# PCB.net
KiCad netlist of a schematic drawn in EAGLE
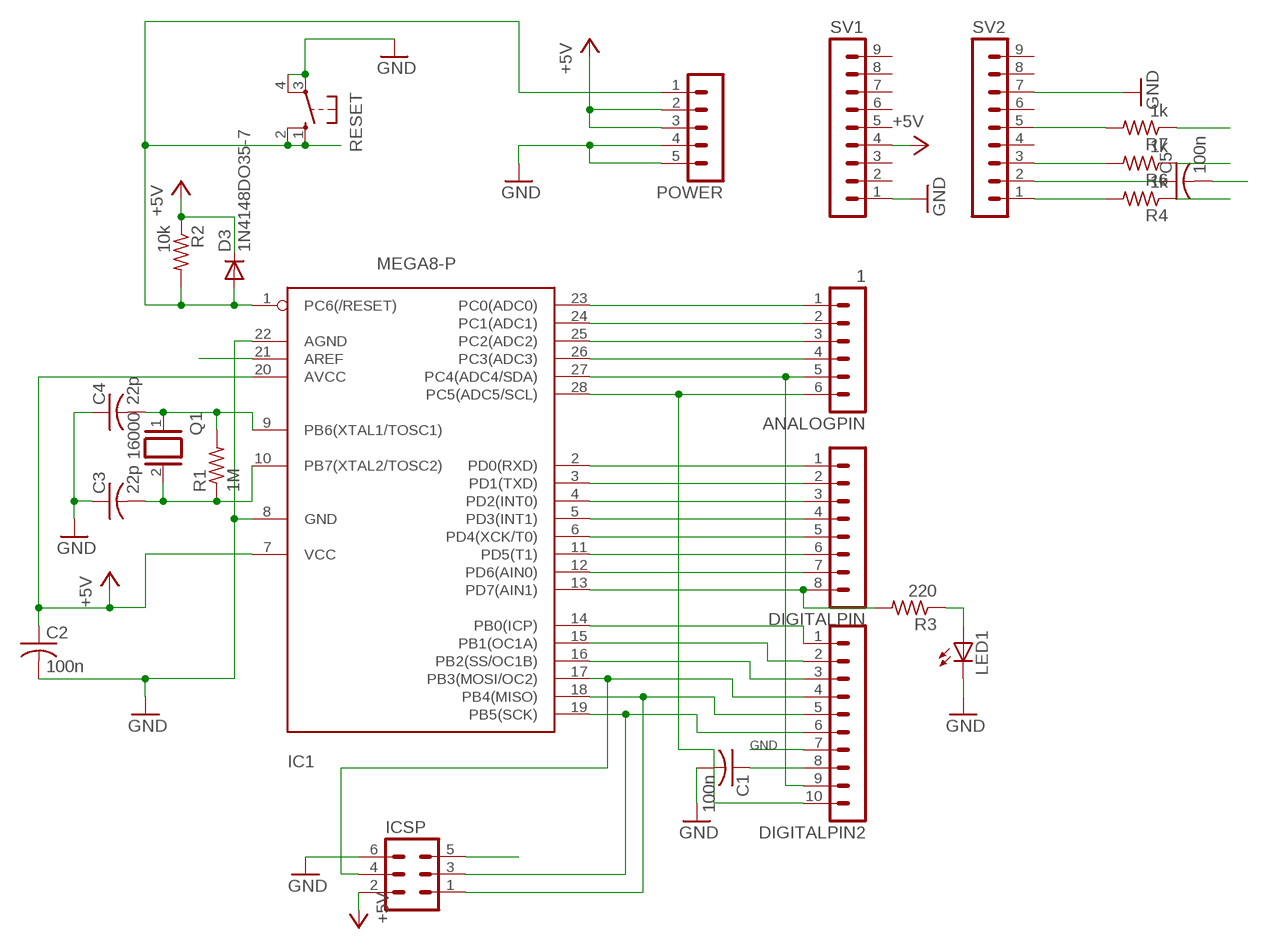
[diagram p0: schematic, sheet 1]

(export (version "E")
  (design (tool "Eeschema 10.0.6"))
  (components
    (comp (ref "ANALOGPIN")
      (value "1")
      (footprint "eagle-import:MA06-1")
      (libsource (lib "eagle-import") (part "MA06-1"))
    )
    (comp (ref "C1")
      (value "100n")
      (footprint "eagle-import:C025-024X044")
      (libsource (lib "eagle-import") (part "C-US025-024X044"))
    )
    (comp (ref "C2")
      (value "100n")
      (footprint "eagle-import:C025-024X044")
      (libsource (lib "eagle-import") (part "C-US025-024X044"))
    )
    (comp (ref "C3")
      (value "22p")
      (footprint "eagle-import:C025-024X044")
      (libsource (lib "eagle-import") (part "C-US025-024X044"))
    )
    (comp (ref "C4")
      (value "22p")
      (footprint "eagle-import:C025-024X044")
      (libsource (lib "eagle-import") (part "C-US025-024X044"))
    )
    (comp (ref "C5")
      (value "100n")
      (footprint "eagle-import:C025-024X044")
      (libsource (lib "eagle-import") (part "C-US025-024X044"))
    )
    (comp (ref "D3")
      (value "1N4148DO35-7")
      (footprint "eagle-import:DO35-7")
      (libsource (lib "eagle-import") (part "1N4148DO35-7"))
    )
    (comp (ref "DIGITALPIN")
      (value "MA08-1")
      (footprint "eagle-import:MA08-1")
      (libsource (lib "eagle-import") (part "MA08-1"))
    )
    (comp (ref "DIGITALPIN2")
      (value "MA10-1")
      (footprint "eagle-import:MA10-1")
      (libsource (lib "eagle-import") (part "MA10-1"))
    )
    (comp (ref "IC1")
      (value "MEGA8-P")
      (footprint "eagle-import:DIL28-3")
      (libsource (lib "eagle-import") (part "MEGA8-P"))
    )
    (comp (ref "ICSP")
      (value "MA03-2")
      (footprint "eagle-import:MA03-2")
      (libsource (lib "eagle-import") (part "MA03-2"))
    )
    (comp (ref "LED1")
      (value "LED3MM")
      (footprint "eagle-import:LED3MM")
      (libsource (lib "eagle-import") (part "LED3MM"))
    )
    (comp (ref "POWER")
      (value "MA05-1")
      (footprint "eagle-import:MA05-1")
      (libsource (lib "eagle-import") (part "MA05-1"))
    )
    (comp (ref "Q1")
      (value "16000")
      (footprint "eagle-import:QS")
      (libsource (lib "eagle-import") (part "XTAL/S"))
    )
    (comp (ref "R1")
      (value "1M")
      (footprint "eagle-import:0204_7")
      (libsource (lib "eagle-import") (part "R-US_0204/7"))
    )
    (comp (ref "R2")
      (value "10k")
      (footprint "eagle-import:0204_7")
      (libsource (lib "eagle-import") (part "R-US_0204/7"))
    )
    (comp (ref "R3")
      (value "220")
      (footprint "eagle-import:0204_7")
      (libsource (lib "eagle-import") (part "R-US_0204/7"))
    )
    (comp (ref "R4")
      (value "1k")
      (footprint "eagle-import:0204_7")
      (libsource (lib "eagle-import") (part "R-US_0204/7"))
    )
    (comp (ref "R6")
      (value "1k")
      (footprint "eagle-import:0204_7")
      (libsource (lib "eagle-import") (part "R-US_0204/7"))
    )
    (comp (ref "R7")
      (value "1k")
      (footprint "eagle-import:0204_7")
      (libsource (lib "eagle-import") (part "R-US_0204/7"))
    )
    (comp (ref "RESET")
      (value "10-XX")
      (footprint "eagle-import:B3F-10XX")
      (libsource (lib "eagle-import") (part "10-XX"))
    )
    (comp (ref "SV1")
      (value "MA09-1")
      (footprint "eagle-import:MA09-1")
      (libsource (lib "eagle-import") (part "MA09-1"))
    )
    (comp (ref "SV2")
      (value "MA09-1")
      (footprint "eagle-import:MA09-1")
      (libsource (lib "eagle-import") (part "MA09-1"))
    )
  )
  (nets
    (net (code "1") (name "+5V") (class "Default")
      (node (ref "C2") (pin "1") (pinfunction "1_1") (pintype "passive"))
      (node (ref "D3") (pin "C") (pinfunction "C_C") (pintype "passive"))
      (node (ref "IC1") (pin "20") (pinfunction "AVCC_20") (pintype "power_in"))
      (node (ref "IC1") (pin "7") (pinfunction "VCC_7") (pintype "power_in"))
      (node (ref "ICSP") (pin "2") (pinfunction "2_2") (pintype "passive"))
      (node (ref "POWER") (pin "2") (pinfunction "2_2") (pintype "passive"))
      (node (ref "POWER") (pin "3") (pinfunction "3_3") (pintype "passive"))
      (node (ref "R2") (pin "1") (pinfunction "1_1") (pintype "passive"))
      (node (ref "SV1") (pin "4") (pinfunction "4_4") (pintype "passive"))
    )
    (net (code "2") (name "/AREF") (class "Default")
      (node (ref "C1") (pin "1") (pinfunction "1_1") (pintype "passive"))
      (node (ref "DIGITALPIN2") (pin "8") (pinfunction "8_8") (pintype "passive"))
      (node (ref "IC1") (pin "21") (pinfunction "AREF_21") (pintype "passive"))
    )
    (net (code "3") (name "/RES1") (class "Default")
      (node (ref "C5") (pin "2") (pinfunction "2_2") (pintype "passive"))
      (node (ref "D3") (pin "A") (pinfunction "A_A") (pintype "passive"))
      (node (ref "IC1") (pin "1") (pinfunction "PC6(/RESET)_1") (pintype "bidirectional"))
      (node (ref "ICSP") (pin "5") (pinfunction "5_5") (pintype "passive"))
      (node (ref "POWER") (pin "1") (pinfunction "1_1") (pintype "passive"))
      (node (ref "R2") (pin "2") (pinfunction "2_2") (pintype "passive"))
      (node (ref "R6") (pin "1") (pinfunction "1_1") (pintype "passive"))
      (node (ref "RESET") (pin "1") (pinfunction "S_1") (pintype "passive"))
      (node (ref "RESET") (pin "2") (pinfunction "S1_2") (pintype "passive"))
    )
    (net (code "4") (name "/RXD") (class "Default")
      (node (ref "DIGITALPIN") (pin "1") (pinfunction "1_1") (pintype "passive"))
      (node (ref "IC1") (pin "2") (pinfunction "PD0(RXD)_2") (pintype "bidirectional"))
      (node (ref "R4") (pin "1") (pinfunction "1_1") (pintype "passive"))
    )
    (net (code "5") (name "/TXD") (class "Default")
      (node (ref "DIGITALPIN") (pin "2") (pinfunction "2_2") (pintype "passive"))
      (node (ref "IC1") (pin "3") (pinfunction "PD1(TXD)_3") (pintype "bidirectional"))
      (node (ref "R7") (pin "1") (pinfunction "1_1") (pintype "passive"))
    )
    (net (code "6") (name "GND") (class "Default")
      (node (ref "C1") (pin "2") (pinfunction "2_2") (pintype "passive"))
      (node (ref "C2") (pin "2") (pinfunction "2_2") (pintype "passive"))
      (node (ref "C3") (pin "1") (pinfunction "1_1") (pintype "passive"))
      (node (ref "C4") (pin "1") (pinfunction "1_1") (pintype "passive"))
      (node (ref "DIGITALPIN2") (pin "7") (pinfunction "7_7") (pintype "passive"))
      (node (ref "IC1") (pin "22") (pinfunction "AGND_22") (pintype "power_in"))
      (node (ref "IC1") (pin "8") (pinfunction "GND_8") (pintype "power_in"))
      (node (ref "ICSP") (pin "6") (pinfunction "6_6") (pintype "passive"))
      (node (ref "LED1") (pin "K") (pinfunction "C_K") (pintype "passive"))
      (node (ref "POWER") (pin "4") (pinfunction "4_4") (pintype "passive"))
      (node (ref "POWER") (pin "5") (pinfunction "5_5") (pintype "passive"))
      (node (ref "RESET") (pin "3") (pinfunction "P_3") (pintype "passive"))
      (node (ref "RESET") (pin "4") (pinfunction "P1_4") (pintype "passive"))
      (node (ref "SV1") (pin "1") (pinfunction "1_1") (pintype "passive"))
      (node (ref "SV2") (pin "7") (pinfunction "7_7") (pintype "passive"))
    )
    (net (code "7") (name "Net-(C5-Pad1)") (class "Default")
      (node (ref "C5") (pin "1") (pinfunction "1_1") (pintype "passive"))
      (node (ref "SV2") (pin "2") (pinfunction "2_2") (pintype "passive"))
    )
    (net (code "8") (name "Net-(IC1-PB0(ICP))") (class "Default")
      (node (ref "DIGITALPIN2") (pin "1") (pinfunction "1_1") (pintype "passive"))
      (node (ref "IC1") (pin "14") (pinfunction "PB0(ICP)_14") (pintype "bidirectional"))
    )
    (net (code "9") (name "Net-(IC1-PB1(OC1A))") (class "Default")
      (node (ref "DIGITALPIN2") (pin "2") (pinfunction "2_2") (pintype "passive"))
      (node (ref "IC1") (pin "15") (pinfunction "PB1(OC1A)_15") (pintype "bidirectional"))
    )
    (net (code "10") (name "Net-(IC1-PB2(SS{slash}OC1B))") (class "Default")
      (node (ref "DIGITALPIN2") (pin "3") (pinfunction "3_3") (pintype "passive"))
      (node (ref "IC1") (pin "16") (pinfunction "PB2(SS/OC1B)_16") (pintype "bidirectional"))
    )
    (net (code "11") (name "Net-(IC1-PB3(MOSI{slash}OC2))") (class "Default")
      (node (ref "DIGITALPIN2") (pin "4") (pinfunction "4_4") (pintype "passive"))
      (node (ref "IC1") (pin "17") (pinfunction "PB3(MOSI/OC2)_17") (pintype "bidirectional"))
      (node (ref "ICSP") (pin "4") (pinfunction "4_4") (pintype "passive"))
    )
    (net (code "12") (name "Net-(IC1-PB4(MISO))") (class "Default")
      (node (ref "DIGITALPIN2") (pin "5") (pinfunction "5_5") (pintype "passive"))
      (node (ref "IC1") (pin "18") (pinfunction "PB4(MISO)_18") (pintype "bidirectional"))
      (node (ref "ICSP") (pin "1") (pinfunction "1_1") (pintype "passive"))
    )
    (net (code "13") (name "Net-(IC1-PB5(SCK))") (class "Default")
      (node (ref "DIGITALPIN2") (pin "6") (pinfunction "6_6") (pintype "passive"))
      (node (ref "IC1") (pin "19") (pinfunction "PB5(SCK)_19") (pintype "bidirectional"))
      (node (ref "ICSP") (pin "3") (pinfunction "3_3") (pintype "passive"))
    )
    (net (code "14") (name "Net-(IC1-PB6(XTAL1{slash}TOSC1))") (class "Default")
      (node (ref "C4") (pin "2") (pinfunction "2_2") (pintype "passive"))
      (node (ref "IC1") (pin "9") (pinfunction "PB6(XTAL1/TOSC1)_9") (pintype "bidirectional"))
      (node (ref "Q1") (pin "1") (pinfunction "1_1") (pintype "passive"))
      (node (ref "R1") (pin "2") (pinfunction "2_2") (pintype "passive"))
    )
    (net (code "15") (name "Net-(IC1-PB7(XTAL2{slash}TOSC2))") (class "Default")
      (node (ref "C3") (pin "2") (pinfunction "2_2") (pintype "passive"))
      (node (ref "IC1") (pin "10") (pinfunction "PB7(XTAL2/TOSC2)_10") (pintype "bidirectional"))
      (node (ref "Q1") (pin "2") (pinfunction "2_2") (pintype "passive"))
      (node (ref "R1") (pin "1") (pinfunction "1_1") (pintype "passive"))
    )
    (net (code "16") (name "Net-(IC1-PC0(ADC0))") (class "Default")
      (node (ref "ANALOGPIN") (pin "1") (pinfunction "1_1") (pintype "passive"))
      (node (ref "IC1") (pin "23") (pinfunction "PC0(ADC0)_23") (pintype "bidirectional"))
    )
    (net (code "17") (name "Net-(IC1-PC1(ADC1))") (class "Default")
      (node (ref "ANALOGPIN") (pin "2") (pinfunction "2_2") (pintype "passive"))
      (node (ref "IC1") (pin "24") (pinfunction "PC1(ADC1)_24") (pintype "bidirectional"))
    )
    (net (code "18") (name "Net-(IC1-PC2(ADC2))") (class "Default")
      (node (ref "ANALOGPIN") (pin "3") (pinfunction "3_3") (pintype "passive"))
      (node (ref "IC1") (pin "25") (pinfunction "PC2(ADC2)_25") (pintype "bidirectional"))
    )
    (net (code "19") (name "Net-(IC1-PC3(ADC3))") (class "Default")
      (node (ref "ANALOGPIN") (pin "4") (pinfunction "4_4") (pintype "passive"))
      (node (ref "IC1") (pin "26") (pinfunction "PC3(ADC3)_26") (pintype "bidirectional"))
    )
    (net (code "20") (name "Net-(IC1-PC4(ADC4{slash}SDA))") (class "Default")
      (node (ref "ANALOGPIN") (pin "5") (pinfunction "5_5") (pintype "passive"))
      (node (ref "DIGITALPIN2") (pin "9") (pinfunction "9_9") (pintype "passive"))
      (node (ref "IC1") (pin "27") (pinfunction "PC4(ADC4/SDA)_27") (pintype "bidirectional"))
    )
    (net (code "21") (name "Net-(IC1-PC5(ADC5{slash}SCL))") (class "Default")
      (node (ref "ANALOGPIN") (pin "6") (pinfunction "6_6") (pintype "passive"))
      (node (ref "DIGITALPIN2") (pin "10") (pinfunction "10_10") (pintype "passive"))
      (node (ref "IC1") (pin "28") (pinfunction "PC5(ADC5/SCL)_28") (pintype "bidirectional"))
    )
    (net (code "22") (name "Net-(IC1-PD2(INT0))") (class "Default")
      (node (ref "DIGITALPIN") (pin "3") (pinfunction "3_3") (pintype "passive"))
      (node (ref "IC1") (pin "4") (pinfunction "PD2(INT0)_4") (pintype "bidirectional"))
    )
    (net (code "23") (name "Net-(IC1-PD3(INT1))") (class "Default")
      (node (ref "DIGITALPIN") (pin "4") (pinfunction "4_4") (pintype "passive"))
      (node (ref "IC1") (pin "5") (pinfunction "PD3(INT1)_5") (pintype "bidirectional"))
    )
    (net (code "24") (name "Net-(IC1-PD4(XCK{slash}T0))") (class "Default")
      (node (ref "DIGITALPIN") (pin "5") (pinfunction "5_5") (pintype "passive"))
      (node (ref "IC1") (pin "6") (pinfunction "PD4(XCK/T0)_6") (pintype "bidirectional"))
    )
    (net (code "25") (name "Net-(IC1-PD5(T1))") (class "Default")
      (node (ref "DIGITALPIN") (pin "6") (pinfunction "6_6") (pintype "passive"))
      (node (ref "IC1") (pin "11") (pinfunction "PD5(T1)_11") (pintype "bidirectional"))
    )
    (net (code "26") (name "Net-(IC1-PD6(AIN0))") (class "Default")
      (node (ref "DIGITALPIN") (pin "7") (pinfunction "7_7") (pintype "passive"))
      (node (ref "IC1") (pin "12") (pinfunction "PD6(AIN0)_12") (pintype "bidirectional"))
    )
    (net (code "27") (name "Net-(IC1-PD7(AIN1))") (class "Default")
      (node (ref "DIGITALPIN") (pin "8") (pinfunction "8_8") (pintype "passive"))
      (node (ref "IC1") (pin "13") (pinfunction "PD7(AIN1)_13") (pintype "bidirectional"))
      (node (ref "R3") (pin "2") (pinfunction "2_2") (pintype "passive"))
    )
    (net (code "28") (name "Net-(LED1-PadA)") (class "Default")
      (node (ref "LED1") (pin "A") (pinfunction "A_A") (pintype "passive"))
      (node (ref "R3") (pin "1") (pinfunction "1_1") (pintype "passive"))
    )
    (net (code "29") (name "Net-(R4-Pad2)") (class "Default")
      (node (ref "R4") (pin "2") (pinfunction "2_2") (pintype "passive"))
      (node (ref "SV2") (pin "1") (pinfunction "1_1") (pintype "passive"))
    )
    (net (code "30") (name "Net-(R6-Pad2)") (class "Default")
      (node (ref "R6") (pin "2") (pinfunction "2_2") (pintype "passive"))
      (node (ref "SV2") (pin "3") (pinfunction "3_3") (pintype "passive"))
    )
    (net (code "31") (name "Net-(R7-Pad2)") (class "Default")
      (node (ref "R7") (pin "2") (pinfunction "2_2") (pintype "passive"))
      (node (ref "SV2") (pin "5") (pinfunction "5_5") (pintype "passive"))
    )
    (net (code "32") (name "unconnected-(SV1-Pad2)") (class "Default")
      (node (ref "SV1") (pin "2") (pinfunction "2_2") (pintype "passive"))
    )
    (net (code "33") (name "unconnected-(SV1-Pad3)") (class "Default")
      (node (ref "SV1") (pin "3") (pinfunction "3_3") (pintype "passive"))
    )
    (net (code "34") (name "unconnected-(SV1-Pad5)") (class "Default")
      (node (ref "SV1") (pin "5") (pinfunction "5_5") (pintype "passive"))
    )
    (net (code "35") (name "unconnected-(SV1-Pad6)") (class "Default")
      (node (ref "SV1") (pin "6") (pinfunction "6_6") (pintype "passive"))
    )
    (net (code "36") (name "unconnected-(SV1-Pad7)") (class "Default")
      (node (ref "SV1") (pin "7") (pinfunction "7_7") (pintype "passive"))
    )
    (net (code "37") (name "unconnected-(SV1-Pad8)") (class "Default")
      (node (ref "SV1") (pin "8") (pinfunction "8_8") (pintype "passive"))
    )
    (net (code "38") (name "unconnected-(SV1-Pad9)") (class "Default")
      (node (ref "SV1") (pin "9") (pinfunction "9_9") (pintype "passive"))
    )
    (net (code "39") (name "unconnected-(SV2-Pad4)") (class "Default")
      (node (ref "SV2") (pin "4") (pinfunction "4_4") (pintype "passive"))
    )
    (net (code "40") (name "unconnected-(SV2-Pad6)") (class "Default")
      (node (ref "SV2") (pin "6") (pinfunction "6_6") (pintype "passive"))
    )
    (net (code "41") (name "unconnected-(SV2-Pad8)") (class "Default")
      (node (ref "SV2") (pin "8") (pinfunction "8_8") (pintype "passive"))
    )
    (net (code "42") (name "unconnected-(SV2-Pad9)") (class "Default")
      (node (ref "SV2") (pin "9") (pinfunction "9_9") (pintype "passive"))
    )
  )
)
